# amc7135-testboard-mk-1_2.net
KiCad netlist of a schematic drawn in EAGLE
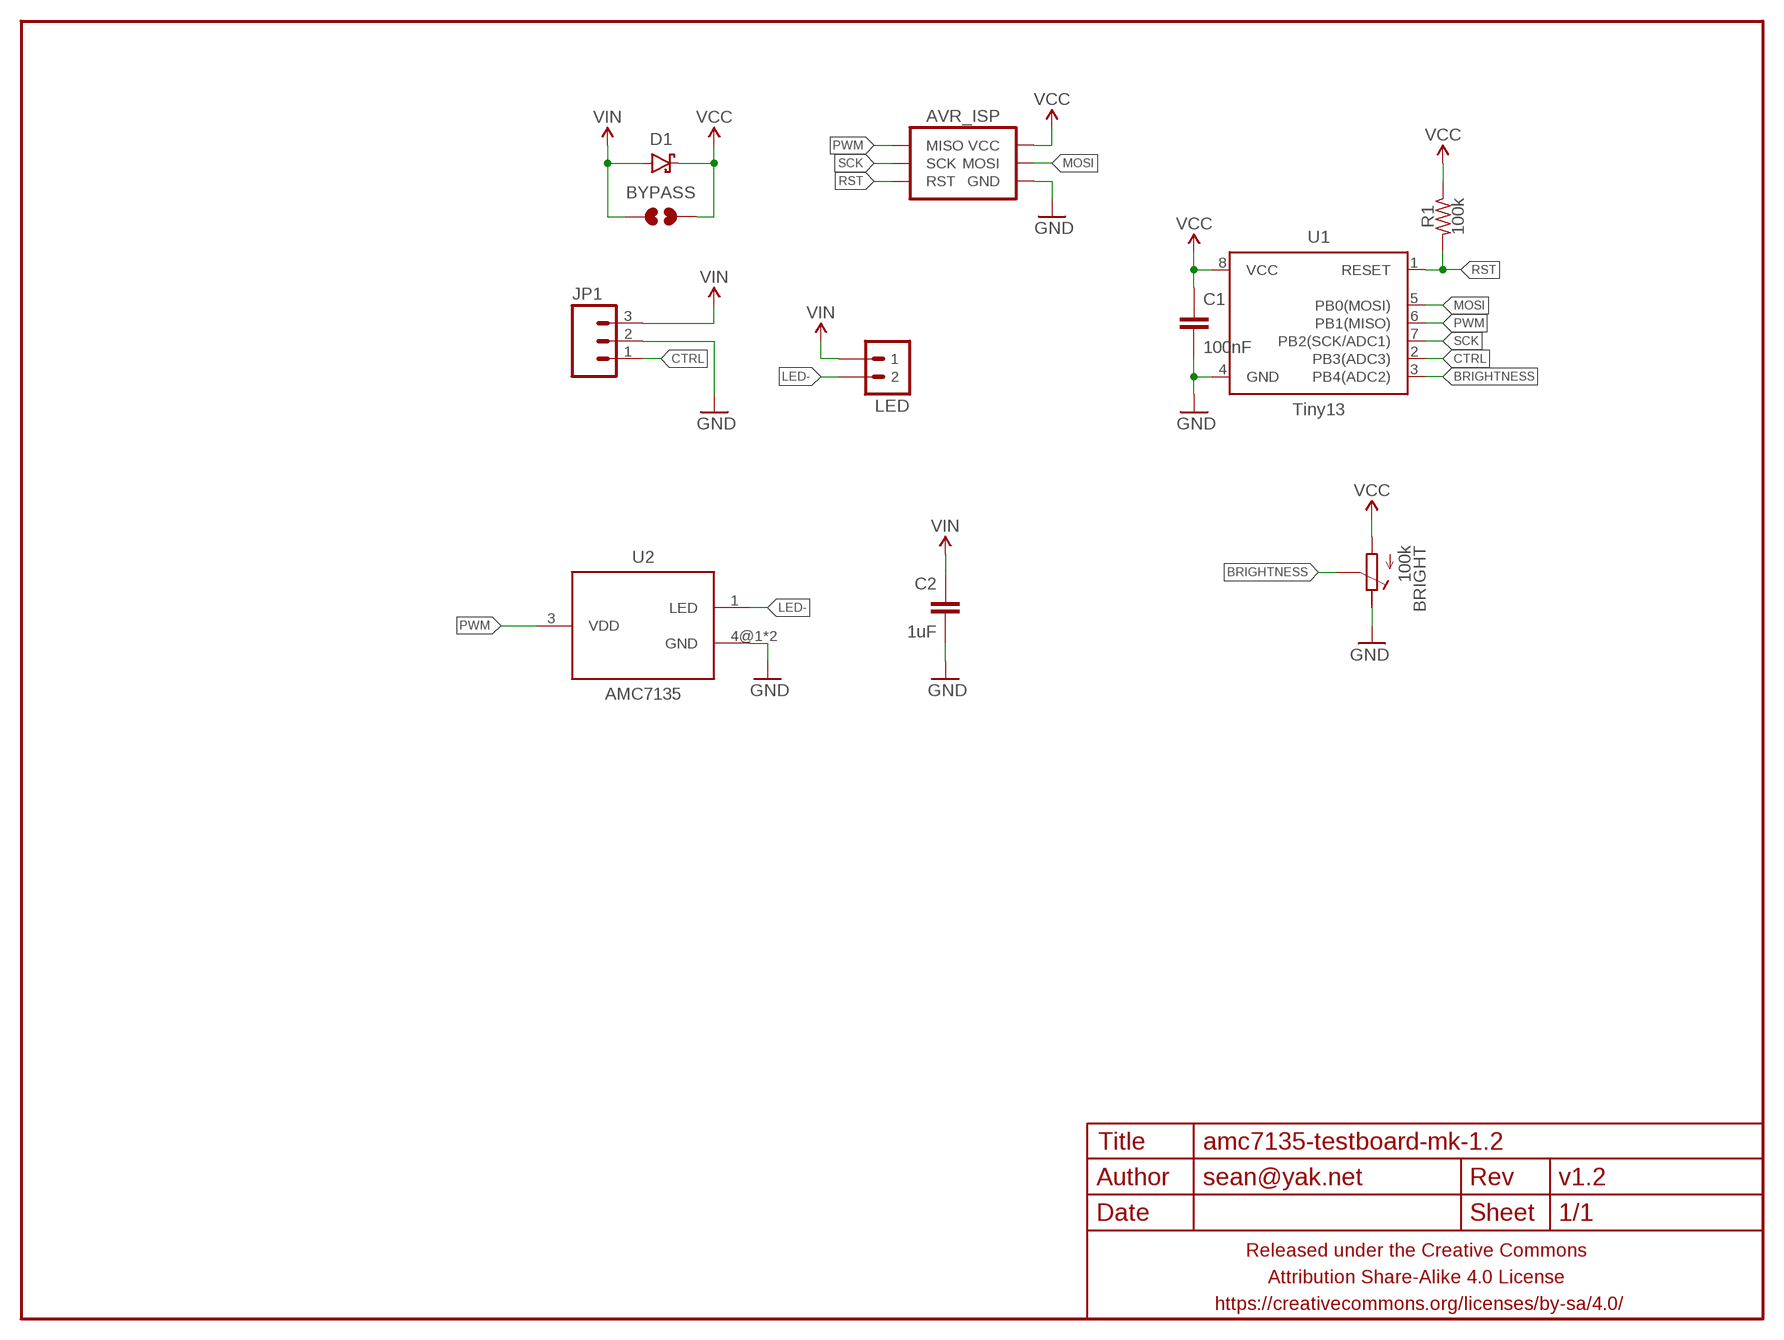
[diagram p0: schematic, sheet 1]

(export (version "E")
  (design (tool "Eeschema 10.0.6"))
  (components
    (comp (ref "AVR_ISP")
      (value "AVR_SPI_PRG_6SMD_TEST_POINTS")
      (footprint "eagle-import:2X3_SMD_TEST_POINTS")
      (libsource (lib "eagle-import") (part "AVR_SPI_PRG_6SMD_TEST_POINTS"))
    )
    (comp (ref "BRIGHT")
      (value "100k")
      (footprint "eagle-import:EVM3Y")
      (libsource (lib "eagle-import") (part "POTENTIOMETEREVM3Y"))
    )
    (comp (ref "BYPASS")
      (value "JUMPER-PAD-2-NOYES_SILK")
      (footprint "eagle-import:PAD-JUMPER-2-NO_YES_SILK")
      (libsource (lib "eagle-import") (part "JUMPER-PAD-2-NOYES_SILK"))
    )
    (comp (ref "C1")
      (value "100nF")
      (footprint "eagle-import:C0603-TIGHTER")
      (libsource (lib "eagle-import") (part "CAPACITOR-CERAMICC0603-TIGHTER"))
    )
    (comp (ref "C2")
      (value "1uF")
      (footprint "eagle-import:C0603-TIGHTER")
      (libsource (lib "eagle-import") (part "CAPACITOR-CERAMICC0603-TIGHTER"))
    )
    (comp (ref "D1")
      (value "DIODE-SCHOTTKYSOD323")
      (footprint "eagle-import:SOD323-SCHOTTKY")
      (libsource (lib "eagle-import") (part "DIODE-SCHOTTKYSOD323"))
    )
    (comp (ref "FRAME1")
      (value "FRAME-LETTERNO_PACKAGE")
      (footprint "eagle-import:DUMMY")
      (fields (field (name "DESIGNER") "sean@yak.net") (field (name "VERSION") "v1.2"))
      (libsource (lib "eagle-import") (part "FRAME-LETTERNO_PACKAGE"))
    )
    (comp (ref "JP1")
      (value "M03PTH-CENTERED")
      (footprint "eagle-import:1X03-CENTERED")
      (libsource (lib "eagle-import") (part "M03PTH-CENTERED"))
    )
    (comp (ref "LED")
      (value "M02PTH-CENTERED")
      (footprint "eagle-import:1X02-CENTER")
      (libsource (lib "eagle-import") (part "M02PTH-CENTERED"))
    )
    (comp (ref "R1")
      (value "100k")
      (footprint "eagle-import:R0603-TIGHTER")
      (libsource (lib "eagle-import") (part "RESISTORR0603-TIGHTER"))
    )
    (comp (ref "U1")
      (value "Tiny13")
      (footprint "eagle-import:SO08")
      (libsource (lib "eagle-import") (part "ATTINY13SOIC"))
    )
    (comp (ref "U2")
      (value "AMC7135")
      (footprint "eagle-import:SOT89-NOTHERM")
      (libsource (lib "eagle-import") (part "AMC7135SOT-89-NOTHERM"))
    )
  )
  (nets
    (net (code "1") (name "BRIGHTNESS") (class "Default")
      (node (ref "BRIGHT") (pin "S") (pinfunction "S_S") (pintype "passive"))
      (node (ref "U1") (pin "3") (pinfunction "PB4(ADC2)_3") (pintype "bidirectional"))
    )
    (net (code "2") (name "CTRL") (class "Default")
      (node (ref "JP1") (pin "1") (pinfunction "1_1") (pintype "passive"))
      (node (ref "U1") (pin "2") (pinfunction "PB3(ADC3)_2") (pintype "bidirectional"))
    )
    (net (code "3") (name "GND") (class "Default")
      (node (ref "AVR_ISP") (pin "6") (pinfunction "GND_6") (pintype "passive"))
      (node (ref "BRIGHT") (pin "E") (pinfunction "E_E") (pintype "passive"))
      (node (ref "C1") (pin "2") (pinfunction "2_2") (pintype "passive"))
      (node (ref "C2") (pin "2") (pinfunction "2_2") (pintype "passive"))
      (node (ref "JP1") (pin "2") (pinfunction "2_2") (pintype "passive"))
      (node (ref "U1") (pin "4") (pinfunction "GND_4") (pintype "bidirectional"))
      (node (ref "U2") (pin "4@1") (pinfunction "GND_4@1") (pintype "bidirectional"))
      (node (ref "U2") (pin "4@2") (pinfunction "GND_4@2") (pintype "bidirectional"))
    )
    (net (code "4") (name "LED-") (class "Default")
      (node (ref "LED") (pin "2") (pinfunction "2_2") (pintype "passive"))
      (node (ref "U2") (pin "1") (pinfunction "LED_1") (pintype "bidirectional"))
    )
    (net (code "5") (name "MOSI") (class "Default")
      (node (ref "AVR_ISP") (pin "4") (pinfunction "MOSI_4") (pintype "passive"))
      (node (ref "U1") (pin "5") (pinfunction "PB0(MOSI)_5") (pintype "bidirectional"))
    )
    (net (code "6") (name "PWM") (class "Default")
      (node (ref "AVR_ISP") (pin "1") (pinfunction "MISO_1") (pintype "passive"))
      (node (ref "U1") (pin "6") (pinfunction "PB1(MISO)_6") (pintype "bidirectional"))
      (node (ref "U2") (pin "3") (pinfunction "VDD_3") (pintype "bidirectional"))
    )
    (net (code "7") (name "RST") (class "Default")
      (node (ref "AVR_ISP") (pin "5") (pinfunction "RST_5") (pintype "passive"))
      (node (ref "R1") (pin "2") (pinfunction "2_2") (pintype "passive"))
      (node (ref "U1") (pin "1") (pinfunction "RESET_1") (pintype "bidirectional"))
    )
    (net (code "8") (name "SCK") (class "Default")
      (node (ref "AVR_ISP") (pin "3") (pinfunction "SCK_3") (pintype "passive"))
      (node (ref "U1") (pin "7") (pinfunction "PB2(SCK/ADC1)_7") (pintype "bidirectional"))
    )
    (net (code "9") (name "VCC") (class "Default")
      (node (ref "AVR_ISP") (pin "2") (pinfunction "VCC_2") (pintype "passive"))
      (node (ref "BRIGHT") (pin "A") (pinfunction "A_A") (pintype "passive"))
      (node (ref "BYPASS") (pin "2") (pinfunction "2_2") (pintype "passive"))
      (node (ref "C1") (pin "1") (pinfunction "1_1") (pintype "passive"))
      (node (ref "D1") (pin "C") (pinfunction "C_C") (pintype "passive"))
      (node (ref "R1") (pin "1") (pinfunction "1_1") (pintype "passive"))
      (node (ref "U1") (pin "8") (pinfunction "VCC_8") (pintype "bidirectional"))
    )
    (net (code "10") (name "VIN") (class "Default")
      (node (ref "BYPASS") (pin "1") (pinfunction "1_1") (pintype "passive"))
      (node (ref "C2") (pin "1") (pinfunction "1_1") (pintype "passive"))
      (node (ref "D1") (pin "A") (pinfunction "A_A") (pintype "passive"))
      (node (ref "JP1") (pin "3") (pinfunction "3_3") (pintype "passive"))
      (node (ref "LED") (pin "1") (pinfunction "1_1") (pintype "passive"))
    )
  )
)
